# Downstream_Controller.net
KiCad netlist of a schematic drawn in Altium Designer
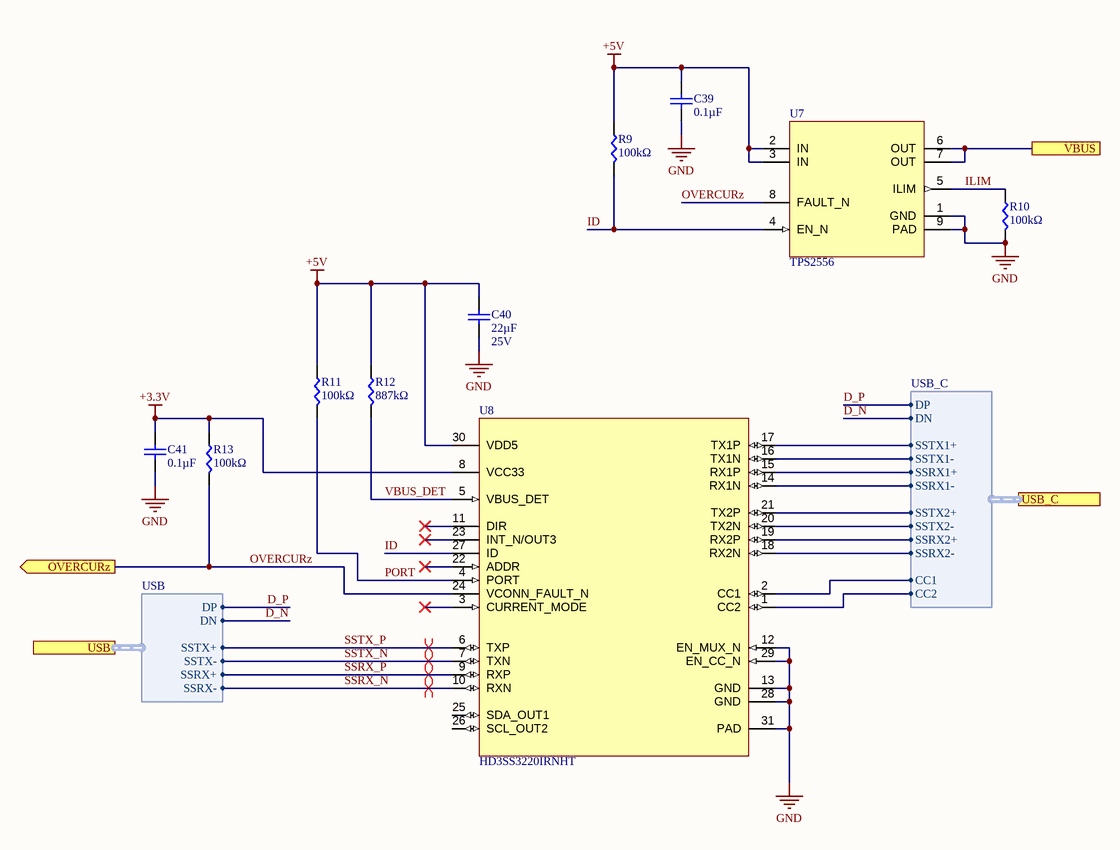
[diagram p0: Downstream_Controller.SchDoc]

(export (version "E")
  (design (tool "Eeschema 10.0.6"))
  (components
    (comp (ref "C39")
      (value "0.1µF")
      (footprint "CAP0402")
      (description "0.1 µF ±10% 50V Ceramic Capacitor X5R 0402 (1005 Metric)")
      (fields (field (name "VOLTAGE") "50V") (field (name "Comment") "CC0402KRX5R9BB104"))
      (libsource (lib "Schlib1") (part "CC0402KRX5R9BB104"))
    )
    (comp (ref "C40")
      (value "22µF")
      (footprint "CAP0805")
      (description "22 µF ±20% 25V Ceramic Capacitor X5R 0805 (2012 Metric)")
      (fields (field (name "VOLTAGE") "25V") (field (name "Comment") "CL21A226MAYNNNE"))
      (libsource (lib "Schlib1") (part "CL21A226MAYNNNE"))
    )
    (comp (ref "C41")
      (value "0.1µF")
      (footprint "CAP0402")
      (description "0.1 µF ±10% 50V Ceramic Capacitor X5R 0402 (1005 Metric)")
      (fields (field (name "VOLTAGE") "50V") (field (name "Comment") "CC0402KRX5R9BB104"))
      (libsource (lib "Schlib1") (part "CC0402KRX5R9BB104"))
    )
    (comp (ref "R9")
      (value "100kΩ")
      (footprint "RES0402")
      (description "100 kOhms ±1% 0.1W, 1/10W Chip Resistor 0402 (1005 Metric) Automotive AEC-Q200 Thick Film")
      (fields (field (name "Comment") "ERJ-2RKF1003X"))
      (libsource (lib "Schlib1") (part "ERJ-2RKF1003X"))
    )
    (comp (ref "R10")
      (value "100kΩ")
      (footprint "RES0402")
      (description "100 kOhms ±1% 0.1W, 1/10W Chip Resistor 0402 (1005 Metric) Automotive AEC-Q200 Thick Film")
      (fields (field (name "Comment") "ERJ-2RKF1003X"))
      (libsource (lib "Schlib1") (part "ERJ-2RKF1003X"))
    )
    (comp (ref "R11")
      (value "100kΩ")
      (footprint "RES0402")
      (description "100 kOhms ±1% 0.1W, 1/10W Chip Resistor 0402 (1005 Metric) Automotive AEC-Q200 Thick Film")
      (fields (field (name "Comment") "ERJ-2RKF1003X"))
      (libsource (lib "Schlib1") (part "ERJ-2RKF1003X"))
    )
    (comp (ref "R12")
      (value "887kΩ")
      (footprint "RES0402")
      (description "887 kOhms ±1% 0.063W, 1/16W Chip Resistor 0402 (1005 Metric) Automotive AEC-Q200 Thick Film")
      (fields (field (name "Comment") "RMCF0402FT887K"))
      (libsource (lib "Schlib1") (part "RMCF0402FT887K"))
    )
    (comp (ref "R13")
      (value "100kΩ")
      (footprint "RES0402")
      (description "100 kOhms ±1% 0.1W, 1/10W Chip Resistor 0402 (1005 Metric) Automotive AEC-Q200 Thick Film")
      (fields (field (name "Comment") "ERJ-2RKF1003X"))
      (libsource (lib "Schlib1") (part "ERJ-2RKF1003X"))
    )
    (comp (ref "U7")
      (value "TPS2556")
      (footprint "8-SON (3x3)")
      (description "Power Switch/Driver 1:1 N-Channel 5A 8-SON (3x3)")
      (fields (field (name "MANUFACTURER") "Texas Instruments"))
      (libsource (lib "Schlib1") (part "TPS2556"))
    )
    (comp (ref "U8")
      (value "HD3SS3220IRNHT")
      (footprint "30-WFQFN Exposed Pad")
      (description "USB, Type-C Controller PMIC 30-WQFN (4.5x2.5)")
      (fields (field (name "MANUFACTURER") "Texas Instruments"))
      (libsource (lib "Schlib1") (part "HD3SS3220IRNHT"))
    )
  )
  (nets
    (net (code "3") (name "+3.3V") (class "Default")
      (node (ref "C41") (pin "2") (pinfunction "2_2") (pintype "passive"))
      (node (ref "R13") (pin "2") (pinfunction "2_2") (pintype "passive"))
      (node (ref "U8") (pin "8") (pinfunction "VCC33_8") (pintype "power_in"))
    )
    (net (code "4") (name "+5V") (class "Default")
      (node (ref "C39") (pin "2") (pinfunction "2_2") (pintype "passive"))
      (node (ref "C40") (pin "2") (pinfunction "2_2") (pintype "passive"))
      (node (ref "R11") (pin "2") (pinfunction "2_2") (pintype "passive"))
      (node (ref "R12") (pin "2") (pinfunction "2_2") (pintype "passive"))
      (node (ref "R9") (pin "2") (pinfunction "2_2") (pintype "passive"))
      (node (ref "U7") (pin "2") (pinfunction "IN_2") (pintype "passive"))
      (node (ref "U7") (pin "3") (pinfunction "IN_3") (pintype "passive"))
      (node (ref "U8") (pin "30") (pinfunction "VDD5_30") (pintype "power_in"))
    )
    (net (code "5") (name "/CC1") (class "Default")
      (node (ref "U8") (pin "2") (pinfunction "CC1_2") (pintype "bidirectional"))
    )
    (net (code "6") (name "/CC2") (class "Default")
      (node (ref "U8") (pin "1") (pinfunction "CC2_1") (pintype "bidirectional"))
    )
    (net (code "9") (name "/ID") (class "Default")
      (node (ref "R9") (pin "1") (pinfunction "1_1") (pintype "passive"))
      (node (ref "U7") (pin "4") (pinfunction "EN_N_4") (pintype "input"))
      (node (ref "U8") (pin "27") (pinfunction "ID_27") (pintype "open_collector"))
    )
    (net (code "10") (name "/ILIM") (class "Default")
      (node (ref "R10") (pin "2") (pinfunction "2_2") (pintype "passive"))
      (node (ref "U7") (pin "5") (pinfunction "ILIM_5") (pintype "output"))
    )
    (net (code "11") (name "/OVERCURz") (class "Default")
      (node (ref "R13") (pin "1") (pinfunction "1_1") (pintype "passive"))
      (node (ref "U7") (pin "8") (pinfunction "FAULT_N_8") (pintype "passive"))
      (node (ref "U8") (pin "24") (pinfunction "VCONN_FAULT_N_24") (pintype "open_collector"))
    )
    (net (code "12") (name "/PORT") (class "Default")
      (node (ref "R11") (pin "1") (pinfunction "1_1") (pintype "passive"))
      (node (ref "U8") (pin "4") (pinfunction "PORT_4") (pintype "input"))
    )
    (net (code "13") (name "/SSRX1+") (class "Default")
      (node (ref "U8") (pin "15") (pinfunction "RX1P_15") (pintype "bidirectional"))
    )
    (net (code "14") (name "/SSRX1-") (class "Default")
      (node (ref "U8") (pin "14") (pinfunction "RX1N_14") (pintype "bidirectional"))
    )
    (net (code "15") (name "/SSRX2+") (class "Default")
      (node (ref "U8") (pin "19") (pinfunction "RX2P_19") (pintype "bidirectional"))
    )
    (net (code "16") (name "/SSRX2-") (class "Default")
      (node (ref "U8") (pin "18") (pinfunction "RX2N_18") (pintype "bidirectional"))
    )
    (net (code "17") (name "/SSRX_N") (class "Default")
      (node (ref "U8") (pin "10") (pinfunction "RXN_10") (pintype "bidirectional"))
    )
    (net (code "18") (name "/SSRX_P") (class "Default")
      (node (ref "U8") (pin "9") (pinfunction "RXP_9") (pintype "bidirectional"))
    )
    (net (code "19") (name "/SSTX1+") (class "Default")
      (node (ref "U8") (pin "17") (pinfunction "TX1P_17") (pintype "bidirectional"))
    )
    (net (code "20") (name "/SSTX1-") (class "Default")
      (node (ref "U8") (pin "16") (pinfunction "TX1N_16") (pintype "bidirectional"))
    )
    (net (code "21") (name "/SSTX2+") (class "Default")
      (node (ref "U8") (pin "21") (pinfunction "TX2P_21") (pintype "bidirectional"))
    )
    (net (code "22") (name "/SSTX2-") (class "Default")
      (node (ref "U8") (pin "20") (pinfunction "TX2N_20") (pintype "bidirectional"))
    )
    (net (code "23") (name "/SSTX_N") (class "Default")
      (node (ref "U8") (pin "7") (pinfunction "TXN_7") (pintype "bidirectional"))
    )
    (net (code "24") (name "/SSTX_P") (class "Default")
      (node (ref "U8") (pin "6") (pinfunction "TXP_6") (pintype "bidirectional"))
    )
    (net (code "25") (name "/VBUS") (class "Default")
      (node (ref "U7") (pin "6") (pinfunction "OUT_6") (pintype "passive"))
      (node (ref "U7") (pin "7") (pinfunction "OUT_7") (pintype "passive"))
    )
    (net (code "26") (name "/VBUS_DET") (class "Default")
      (node (ref "R12") (pin "1") (pinfunction "1_1") (pintype "passive"))
      (node (ref "U8") (pin "5") (pinfunction "VBUS_DET_5") (pintype "input"))
    )
    (net (code "29") (name "GND") (class "Default")
      (node (ref "C39") (pin "1") (pinfunction "1_1") (pintype "passive"))
      (node (ref "C40") (pin "1") (pinfunction "1_1") (pintype "passive"))
      (node (ref "C41") (pin "1") (pinfunction "1_1") (pintype "passive"))
      (node (ref "R10") (pin "1") (pinfunction "1_1") (pintype "passive"))
      (node (ref "U7") (pin "1") (pinfunction "GND_1") (pintype "passive"))
      (node (ref "U7") (pin "9") (pinfunction "PAD_9") (pintype "passive"))
      (node (ref "U8") (pin "12") (pinfunction "EN_MUX_N_12") (pintype "input"))
      (node (ref "U8") (pin "13") (pinfunction "GND_13") (pintype "power_in"))
      (node (ref "U8") (pin "28") (pinfunction "GND_28") (pintype "power_in"))
      (node (ref "U8") (pin "29") (pinfunction "EN_CC_N_29") (pintype "input"))
      (node (ref "U8") (pin "31") (pinfunction "PAD_31") (pintype "power_in"))
    )
    (net (code "30") (name "unconnected-(U8-ADDR-Pad22)") (class "Default")
      (node (ref "U8") (pin "22") (pinfunction "ADDR_22") (pintype "input+no_connect"))
    )
    (net (code "31") (name "unconnected-(U8-CURRENT_MODE-Pad3)") (class "Default")
      (node (ref "U8") (pin "3") (pinfunction "CURRENT_MODE_3") (pintype "input+no_connect"))
    )
    (net (code "32") (name "unconnected-(U8-DIR-Pad11)") (class "Default")
      (node (ref "U8") (pin "11") (pinfunction "DIR_11") (pintype "open_collector+no_connect"))
    )
    (net (code "33") (name "unconnected-(U8-INT_N{slash}OUT3-Pad23)") (class "Default")
      (node (ref "U8") (pin "23") (pinfunction "INT_N/OUT3_23") (pintype "open_collector+no_connect"))
    )
    (net (code "34") (name "unconnected-(U8-SCL_OUT2-Pad26)") (class "Default")
      (node (ref "U8") (pin "26") (pinfunction "SCL_OUT2_26") (pintype "bidirectional"))
    )
    (net (code "35") (name "unconnected-(U8-SDA_OUT1-Pad25)") (class "Default")
      (node (ref "U8") (pin "25") (pinfunction "SDA_OUT1_25") (pintype "bidirectional"))
    )
  )
)
